# DDC118_eval2_rev1F.net
KiCad netlist of a schematic drawn in EAGLE
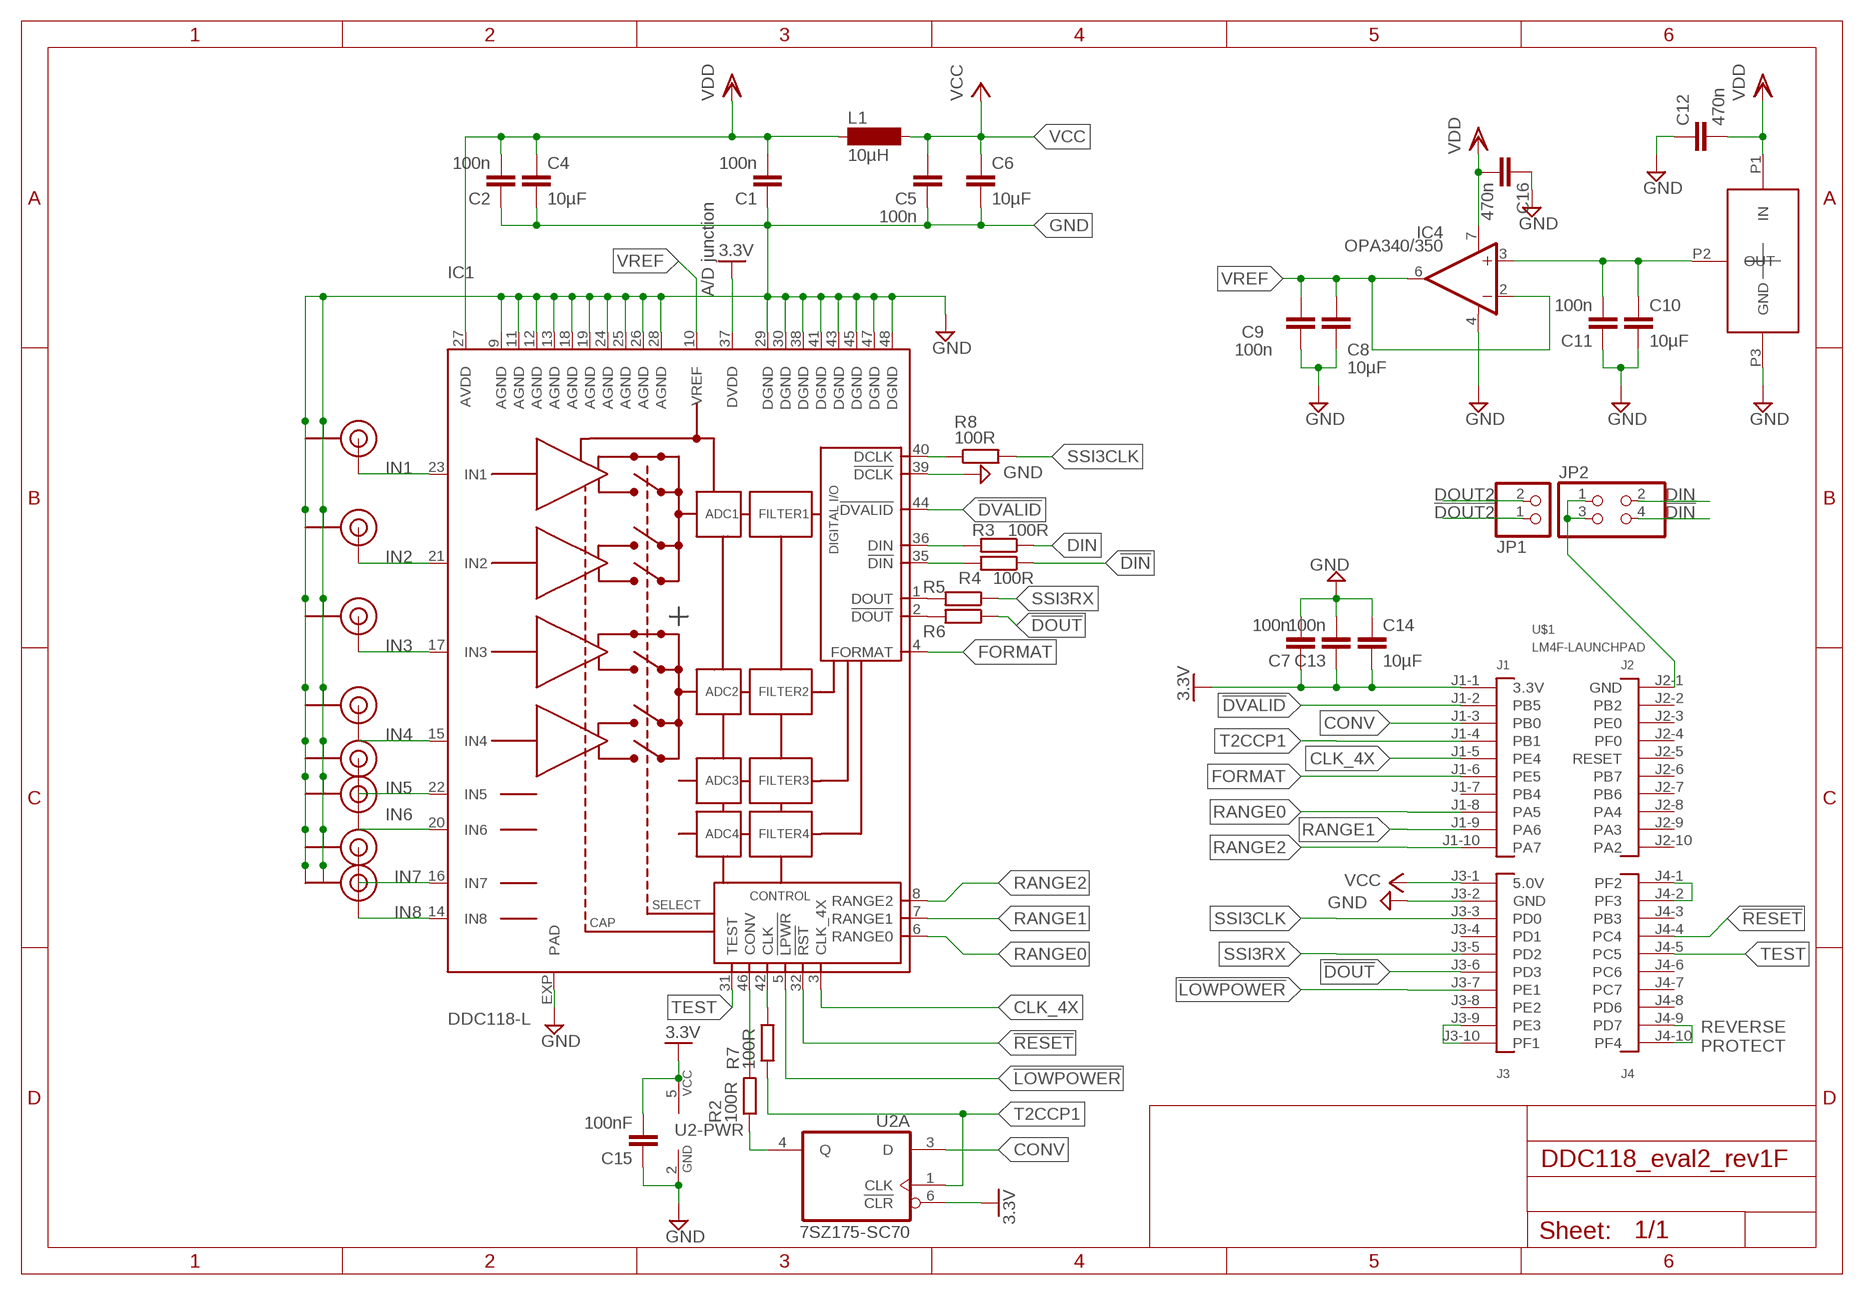
[diagram p0: schematic, sheet 1]

(export (version "E")
  (design (tool "Eeschema 10.0.6"))
  (components
    (comp (ref "C1")
      (value "100n")
      (footprint "eagle-import:C0805K")
      (libsource (lib "eagle-import") (part "C-EUC0805K"))
    )
    (comp (ref "C2")
      (value "100n")
      (footprint "eagle-import:C0805K")
      (libsource (lib "eagle-import") (part "C-EUC0805K"))
    )
    (comp (ref "C4")
      (value "10µF")
      (footprint "eagle-import:C0805")
      (libsource (lib "eagle-import") (part "C-EUC0805"))
    )
    (comp (ref "C5")
      (value "100n")
      (footprint "eagle-import:C0805K")
      (libsource (lib "eagle-import") (part "C-EUC0805K"))
    )
    (comp (ref "C6")
      (value "10µF")
      (footprint "eagle-import:C0805")
      (libsource (lib "eagle-import") (part "C-EUC0805"))
    )
    (comp (ref "C7")
      (value "100n")
      (footprint "eagle-import:C0805K")
      (libsource (lib "eagle-import") (part "C-EUC0805K"))
    )
    (comp (ref "C8")
      (value "10µF")
      (footprint "eagle-import:C0805")
      (libsource (lib "eagle-import") (part "C-EUC0805"))
    )
    (comp (ref "C9")
      (value "100n")
      (footprint "eagle-import:C0805K")
      (libsource (lib "eagle-import") (part "C-EUC0805K"))
    )
    (comp (ref "C10")
      (value "10µF")
      (footprint "eagle-import:C0805")
      (libsource (lib "eagle-import") (part "C-EUC0805"))
    )
    (comp (ref "C11")
      (value "100n")
      (footprint "eagle-import:C0805K")
      (libsource (lib "eagle-import") (part "C-EUC0805K"))
    )
    (comp (ref "C12")
      (value "470n")
      (footprint "eagle-import:C0805K")
      (libsource (lib "eagle-import") (part "C-EUC0805K"))
    )
    (comp (ref "C13")
      (value "100n")
      (footprint "eagle-import:C0805K")
      (libsource (lib "eagle-import") (part "C-EUC0805K"))
    )
    (comp (ref "C14")
      (value "10µF")
      (footprint "eagle-import:C0805")
      (libsource (lib "eagle-import") (part "C-EUC0805"))
    )
    (comp (ref "C15")
      (value "100nF")
      (footprint "eagle-import:C0603K")
      (libsource (lib "eagle-import") (part "resistor_C-EUC0603K"))
    )
    (comp (ref "C16")
      (value "470n")
      (footprint "eagle-import:0805")
      (libsource (lib "eagle-import") (part "CAP0805"))
    )
    (comp (ref "IC1")
      (value "DDC118-L")
      (footprint "eagle-import:VQFN48-L")
      (libsource (lib "eagle-import") (part "DDC118-L"))
    )
    (comp (ref "IC4")
      (value "OPA340/350")
      (footprint "eagle-import:SO08")
      (fields (field (name "MPN") "OPA340UA"))
      (libsource (lib "eagle-import") (part "OPA340U"))
    )
    (comp (ref "JP1")
      (value "PINHD-1X2_2.54-SMD")
      (footprint "eagle-import:1X02SMD")
      (libsource (lib "eagle-import") (part "PINHD-1X2_2.54-SMD"))
    )
    (comp (ref "JP2")
      (value "PINHD-2X2_2.54-SMD")
      (footprint "eagle-import:2X02SMD")
      (libsource (lib "eagle-import") (part "PINHD-2X2_2.54-SMD"))
    )
    (comp (ref "L1")
      (value "10µH")
      (footprint "eagle-import:MS50")
      (libsource (lib "eagle-import") (part "MS50"))
    )
    (comp (ref "R2")
      (value "100R")
      (footprint "eagle-import:R0402")
      (libsource (lib "eagle-import") (part "R-EU_R0402"))
    )
    (comp (ref "R3")
      (value "100R")
      (footprint "eagle-import:R0402")
      (libsource (lib "eagle-import") (part "R-EU_R0402"))
    )
    (comp (ref "R4")
      (value "100R")
      (footprint "eagle-import:R0402")
      (libsource (lib "eagle-import") (part "R-EU_R0402"))
    )
    (comp (ref "R5")
      (value "100R")
      (footprint "eagle-import:R0402")
      (libsource (lib "eagle-import") (part "R-EU_R0402"))
    )
    (comp (ref "R6")
      (value "100R")
      (footprint "eagle-import:R0402")
      (libsource (lib "eagle-import") (part "R-EU_R0402"))
    )
    (comp (ref "R7")
      (value "100R")
      (footprint "eagle-import:R0402")
      (libsource (lib "eagle-import") (part "R-EU_R0402"))
    )
    (comp (ref "R8")
      (value "100R")
      (footprint "eagle-import:R0402")
      (libsource (lib "eagle-import") (part "R-EU_R0402"))
    )
    (comp (ref "U$1")
      (value "LM4F-LAUNCHPAD")
      (footprint "eagle-import:LM4F120-LAUNCHPAD")
      (libsource (lib "eagle-import") (part "LM4F-LAUNCHPAD"))
    )
    (comp (ref "U$4")
      (value "U.FL")
      (footprint "eagle-import:U.FL")
      (libsource (lib "eagle-import") (part "U.FL"))
    )
    (comp (ref "U$5")
      (value "U.FL")
      (footprint "eagle-import:U.FL")
      (libsource (lib "eagle-import") (part "U.FL"))
    )
    (comp (ref "U$6")
      (value "U.FL")
      (footprint "eagle-import:U.FL")
      (libsource (lib "eagle-import") (part "U.FL"))
    )
    (comp (ref "U$7")
      (value "U.FL")
      (footprint "eagle-import:U.FL")
      (libsource (lib "eagle-import") (part "U.FL"))
    )
    (comp (ref "U$8")
      (value "U.FL")
      (footprint "eagle-import:U.FL")
      (libsource (lib "eagle-import") (part "U.FL"))
    )
    (comp (ref "U$9")
      (value "U.FL")
      (footprint "eagle-import:U.FL")
      (libsource (lib "eagle-import") (part "U.FL"))
    )
    (comp (ref "U$10")
      (value "U.FL")
      (footprint "eagle-import:U.FL")
      (libsource (lib "eagle-import") (part "U.FL"))
    )
    (comp (ref "U$11")
      (value "U.FL")
      (footprint "eagle-import:U.FL")
      (libsource (lib "eagle-import") (part "U.FL"))
    )
    (comp (ref "U1")
      (value "REF30XX")
      (footprint "eagle-import:SOT-23")
      (libsource (lib "eagle-import") (part "REF30XX"))
    )
    (comp (ref "U2")
      (value "7SZ175-SC70")
      (footprint "eagle-import:SC-70")
      (libsource (lib "eagle-import") (part "7SZ175-SC70"))
    )
  )
  (nets
    (net (code "1") (name "/DOUT2") (class "Default")
      (node (ref "JP1") (pin "2") (pinfunction "2_2") (pintype "passive"))
    )
    (net (code "2") (name "/IN1") (class "Default")
      (node (ref "IC1") (pin "23") (pinfunction "IN1_23") (pintype "input"))
      (node (ref "U$5") (pin "P$3") (pinfunction "SIGNAL_P$3") (pintype "bidirectional"))
    )
    (net (code "3") (name "/IN2") (class "Default")
      (node (ref "IC1") (pin "21") (pinfunction "IN2_21") (pintype "input"))
      (node (ref "U$6") (pin "P$3") (pinfunction "SIGNAL_P$3") (pintype "bidirectional"))
    )
    (net (code "4") (name "/IN3") (class "Default")
      (node (ref "IC1") (pin "17") (pinfunction "IN3_17") (pintype "input"))
      (node (ref "U$7") (pin "P$3") (pinfunction "SIGNAL_P$3") (pintype "bidirectional"))
    )
    (net (code "5") (name "/IN4") (class "Default")
      (node (ref "IC1") (pin "15") (pinfunction "IN4_15") (pintype "input"))
      (node (ref "U$8") (pin "P$3") (pinfunction "SIGNAL_P$3") (pintype "bidirectional"))
    )
    (net (code "6") (name "/IN5") (class "Default")
      (node (ref "IC1") (pin "22") (pinfunction "IN5_22") (pintype "input"))
      (node (ref "U$9") (pin "P$3") (pinfunction "SIGNAL_P$3") (pintype "bidirectional"))
    )
    (net (code "7") (name "/IN6") (class "Default")
      (node (ref "IC1") (pin "20") (pinfunction "IN6_20") (pintype "input"))
      (node (ref "U$4") (pin "P$3") (pinfunction "SIGNAL_P$3") (pintype "bidirectional"))
    )
    (net (code "8") (name "/IN7") (class "Default")
      (node (ref "IC1") (pin "16") (pinfunction "IN7_16") (pintype "input"))
      (node (ref "U$11") (pin "P$3") (pinfunction "SIGNAL_P$3") (pintype "bidirectional"))
    )
    (net (code "9") (name "/IN8") (class "Default")
      (node (ref "IC1") (pin "14") (pinfunction "IN8_14") (pintype "input"))
      (node (ref "U$10") (pin "P$3") (pinfunction "SIGNAL_P$3") (pintype "bidirectional"))
    )
    (net (code "10") (name "/~{DIN}") (class "Default")
      (node (ref "JP2") (pin "4") (pinfunction "4_4") (pintype "passive"))
      (node (ref "R4") (pin "1") (pinfunction "1_1") (pintype "passive"))
    )
    (net (code "11") (name "/~{DOUT2}") (class "Default")
      (node (ref "JP1") (pin "1") (pinfunction "1_1") (pintype "passive"))
    )
    (net (code "12") (name "/~{DOUT}") (class "Default")
      (node (ref "R6") (pin "1") (pinfunction "1_1") (pintype "passive"))
      (node (ref "U$1") (pin "J3-6") (pinfunction "PD3_J3-6") (pintype "bidirectional"))
    )
    (net (code "13") (name "/~{DVALID}") (class "Default")
      (node (ref "IC1") (pin "44") (pinfunction "~{DVALID}_44") (pintype "output"))
      (node (ref "U$1") (pin "J1-2") (pinfunction "PB5_J1-2") (pintype "bidirectional"))
    )
    (net (code "14") (name "/~{LOWPOWER}") (class "Default")
      (node (ref "IC1") (pin "5") (pinfunction "~{LPWR}_5") (pintype "input"))
      (node (ref "U$1") (pin "J3-7") (pinfunction "PE1_J3-7") (pintype "bidirectional"))
    )
    (net (code "15") (name "/~{RESET}") (class "Default")
      (node (ref "IC1") (pin "32") (pinfunction "~{RST}_32") (pintype "input"))
      (node (ref "U$1") (pin "J4-4") (pinfunction "PC4_J4-4") (pintype "bidirectional"))
    )
    (net (code "16") (name "3.3V") (class "Default")
      (node (ref "C13") (pin "1") (pinfunction "1_1") (pintype "passive"))
      (node (ref "C14") (pin "2") (pinfunction "2_2") (pintype "passive"))
      (node (ref "C15") (pin "2") (pinfunction "2_2") (pintype "passive"))
      (node (ref "C7") (pin "1") (pinfunction "1_1") (pintype "passive"))
      (node (ref "IC1") (pin "37") (pinfunction "DVDD_37") (pintype "power_in"))
      (node (ref "U$1") (pin "J1-1") (pinfunction "3.3V_J1-1") (pintype "power_in"))
      (node (ref "U2") (pin "5") (pinfunction "VCC_5") (pintype "power_in"))
      (node (ref "U2") (pin "6") (pinfunction "~{CLR}_6") (pintype "input"))
    )
    (net (code "17") (name "CLK_4X") (class "Default")
      (node (ref "IC1") (pin "3") (pinfunction "CLK_4X_3") (pintype "input"))
      (node (ref "U$1") (pin "J1-5") (pinfunction "PE4_J1-5") (pintype "bidirectional"))
    )
    (net (code "18") (name "CONV") (class "Default")
      (node (ref "U$1") (pin "J1-3") (pinfunction "PB0_J1-3") (pintype "bidirectional"))
      (node (ref "U2") (pin "3") (pinfunction "D_3") (pintype "input"))
    )
    (net (code "19") (name "DIN") (class "Default")
      (node (ref "JP2") (pin "2") (pinfunction "2_2") (pintype "passive"))
      (node (ref "R3") (pin "1") (pinfunction "1_1") (pintype "passive"))
    )
    (net (code "20") (name "FORMAT") (class "Default")
      (node (ref "IC1") (pin "4") (pinfunction "FORMAT_4") (pintype "output"))
      (node (ref "U$1") (pin "J1-6") (pinfunction "PE5_J1-6") (pintype "bidirectional"))
    )
    (net (code "21") (name "GND") (class "Default")
      (node (ref "C1") (pin "1") (pinfunction "1_1") (pintype "passive"))
      (node (ref "C10") (pin "2") (pinfunction "2_2") (pintype "passive"))
      (node (ref "C11") (pin "1") (pinfunction "1_1") (pintype "passive"))
      (node (ref "C12") (pin "1") (pinfunction "1_1") (pintype "passive"))
      (node (ref "C13") (pin "2") (pinfunction "2_2") (pintype "passive"))
      (node (ref "C14") (pin "1") (pinfunction "1_1") (pintype "passive"))
      (node (ref "C15") (pin "1") (pinfunction "1_1") (pintype "passive"))
      (node (ref "C16") (pin "1") (pinfunction "1_1") (pintype "passive"))
      (node (ref "C2") (pin "1") (pinfunction "1_1") (pintype "passive"))
      (node (ref "C4") (pin "2") (pinfunction "2_2") (pintype "passive"))
      (node (ref "C5") (pin "1") (pinfunction "1_1") (pintype "passive"))
      (node (ref "C6") (pin "2") (pinfunction "2_2") (pintype "passive"))
      (node (ref "C7") (pin "2") (pinfunction "2_2") (pintype "passive"))
      (node (ref "C8") (pin "2") (pinfunction "2_2") (pintype "passive"))
      (node (ref "C9") (pin "1") (pinfunction "1_1") (pintype "passive"))
      (node (ref "IC1") (pin "11") (pinfunction "AGND_11") (pintype "power_in"))
      (node (ref "IC1") (pin "12") (pinfunction "AGND_12") (pintype "power_in"))
      (node (ref "IC1") (pin "13") (pinfunction "AGND_13") (pintype "power_in"))
      (node (ref "IC1") (pin "18") (pinfunction "AGND_18") (pintype "power_in"))
      (node (ref "IC1") (pin "19") (pinfunction "AGND_19") (pintype "power_in"))
      (node (ref "IC1") (pin "24") (pinfunction "AGND_24") (pintype "power_in"))
      (node (ref "IC1") (pin "25") (pinfunction "AGND_25") (pintype "power_in"))
      (node (ref "IC1") (pin "26") (pinfunction "AGND_26") (pintype "power_in"))
      (node (ref "IC1") (pin "28") (pinfunction "AGND_28") (pintype "power_in"))
      (node (ref "IC1") (pin "29") (pinfunction "DGND_29") (pintype "power_in"))
      (node (ref "IC1") (pin "30") (pinfunction "DGND_30") (pintype "power_in"))
      (node (ref "IC1") (pin "38") (pinfunction "DGND_38") (pintype "power_in"))
      (node (ref "IC1") (pin "39") (pinfunction "~{DCLK}_39") (pintype "input"))
      (node (ref "IC1") (pin "41") (pinfunction "DGND_41") (pintype "power_in"))
      (node (ref "IC1") (pin "43") (pinfunction "DGND_43") (pintype "power_in"))
      (node (ref "IC1") (pin "45") (pinfunction "DGND_45") (pintype "power_in"))
      (node (ref "IC1") (pin "47") (pinfunction "DGND_47") (pintype "power_in"))
      (node (ref "IC1") (pin "48") (pinfunction "DGND_48") (pintype "power_in"))
      (node (ref "IC1") (pin "9") (pinfunction "AGND_9") (pintype "power_in"))
      (node (ref "IC1") (pin "EXP") (pinfunction "PAD_EXP") (pintype "power_in"))
      (node (ref "IC4") (pin "4") (pinfunction "V-_4") (pintype "power_in"))
      (node (ref "U$1") (pin "J3-2") (pinfunction "GND_J3-2") (pintype "bidirectional"))
      (node (ref "U$10") (pin "P$1") (pinfunction "GND_P$1") (pintype "bidirectional"))
      (node (ref "U$10") (pin "P$2") (pinfunction "GND_P$2") (pintype "bidirectional"))
      (node (ref "U$11") (pin "P$1") (pinfunction "GND_P$1") (pintype "bidirectional"))
      (node (ref "U$11") (pin "P$2") (pinfunction "GND_P$2") (pintype "bidirectional"))
      (node (ref "U$4") (pin "P$1") (pinfunction "GND_P$1") (pintype "bidirectional"))
      (node (ref "U$4") (pin "P$2") (pinfunction "GND_P$2") (pintype "bidirectional"))
      (node (ref "U$5") (pin "P$1") (pinfunction "GND_P$1") (pintype "bidirectional"))
      (node (ref "U$5") (pin "P$2") (pinfunction "GND_P$2") (pintype "bidirectional"))
      (node (ref "U$6") (pin "P$1") (pinfunction "GND_P$1") (pintype "bidirectional"))
      (node (ref "U$6") (pin "P$2") (pinfunction "GND_P$2") (pintype "bidirectional"))
      (node (ref "U$7") (pin "P$1") (pinfunction "GND_P$1") (pintype "bidirectional"))
      (node (ref "U$7") (pin "P$2") (pinfunction "GND_P$2") (pintype "bidirectional"))
      (node (ref "U$8") (pin "P$1") (pinfunction "GND_P$1") (pintype "bidirectional"))
      (node (ref "U$8") (pin "P$2") (pinfunction "GND_P$2") (pintype "bidirectional"))
      (node (ref "U$9") (pin "P$1") (pinfunction "GND_P$1") (pintype "bidirectional"))
      (node (ref "U$9") (pin "P$2") (pinfunction "GND_P$2") (pintype "bidirectional"))
      (node (ref "U1") (pin "P3") (pinfunction "GND_P3") (pintype "bidirectional"))
      (node (ref "U2") (pin "2") (pinfunction "GND_2") (pintype "power_in"))
    )
    (net (code "22") (name "Net-(IC1-CLK)") (class "Default")
      (node (ref "IC1") (pin "42") (pinfunction "CLK_42") (pintype "input"))
      (node (ref "R7") (pin "2") (pinfunction "2_2") (pintype "passive"))
    )
    (net (code "23") (name "Net-(IC1-CONV)") (class "Default")
      (node (ref "IC1") (pin "46") (pinfunction "CONV_46") (pintype "input"))
      (node (ref "R2") (pin "2") (pinfunction "2_2") (pintype "passive"))
    )
    (net (code "24") (name "Net-(IC1-DCLK)") (class "Default")
      (node (ref "IC1") (pin "40") (pinfunction "DCLK_40") (pintype "input"))
      (node (ref "R8") (pin "1") (pinfunction "1_1") (pintype "passive"))
    )
    (net (code "25") (name "Net-(IC1-DIN)") (class "Default")
      (node (ref "IC1") (pin "36") (pinfunction "DIN_36") (pintype "input"))
      (node (ref "R3") (pin "2") (pinfunction "2_2") (pintype "passive"))
    )
    (net (code "26") (name "Net-(IC1-DOUT)") (class "Default")
      (node (ref "IC1") (pin "1") (pinfunction "DOUT_1") (pintype "output"))
      (node (ref "R5") (pin "2") (pinfunction "2_2") (pintype "passive"))
    )
    (net (code "27") (name "Net-(IC1-~{DIN})") (class "Default")
      (node (ref "IC1") (pin "35") (pinfunction "~{DIN}_35") (pintype "input"))
      (node (ref "R4") (pin "2") (pinfunction "2_2") (pintype "passive"))
    )
    (net (code "28") (name "Net-(IC1-~{DOUT})") (class "Default")
      (node (ref "IC1") (pin "2") (pinfunction "~{DOUT}_2") (pintype "output"))
      (node (ref "R6") (pin "2") (pinfunction "2_2") (pintype "passive"))
    )
    (net (code "29") (name "Net-(IC4-+IN)") (class "Default")
      (node (ref "C10") (pin "1") (pinfunction "1_1") (pintype "passive"))
      (node (ref "C11") (pin "2") (pinfunction "2_2") (pintype "passive"))
      (node (ref "IC4") (pin "3") (pinfunction "+IN_3") (pintype "input"))
      (node (ref "U1") (pin "P2") (pinfunction "OUT_P2") (pintype "bidirectional"))
    )
    (net (code "30") (name "Net-(JP2-Pad1)") (class "Default")
      (node (ref "JP2") (pin "1") (pinfunction "1_1") (pintype "passive"))
      (node (ref "JP2") (pin "3") (pinfunction "3_3") (pintype "passive"))
      (node (ref "U$1") (pin "J2-1") (pinfunction "GND_J2-1") (pintype "power_in"))
    )
    (net (code "31") (name "Net-(U$1-PD7)") (class "Default")
      (node (ref "U$1") (pin "J4-10") (pinfunction "PF4_J4-10") (pintype "bidirectional"))
      (node (ref "U$1") (pin "J4-9") (pinfunction "PD7_J4-9") (pintype "bidirectional"))
    )
    (net (code "32") (name "Net-(U$1-PE3)") (class "Default")
      (node (ref "U$1") (pin "J3-10") (pinfunction "PF1_J3-10") (pintype "bidirectional"))
      (node (ref "U$1") (pin "J3-9") (pinfunction "PE3_J3-9") (pintype "bidirectional"))
    )
    (net (code "33") (name "Net-(U$1-PF2)") (class "Default")
      (node (ref "U$1") (pin "J4-1") (pinfunction "PF2_J4-1") (pintype "power_in"))
      (node (ref "U$1") (pin "J4-2") (pinfunction "PF3_J4-2") (pintype "bidirectional"))
    )
    (net (code "34") (name "Net-(U2B-Q)") (class "Default")
      (node (ref "R2") (pin "1") (pinfunction "1_1") (pintype "passive"))
      (node (ref "U2") (pin "4") (pinfunction "Q_4") (pintype "output"))
    )
    (net (code "35") (name "RANGE0") (class "Default")
      (node (ref "IC1") (pin "6") (pinfunction "RANGE0_6") (pintype "output"))
      (node (ref "U$1") (pin "J1-8") (pinfunction "PA5_J1-8") (pintype "bidirectional"))
    )
    (net (code "36") (name "RANGE1") (class "Default")
      (node (ref "IC1") (pin "7") (pinfunction "RANGE1_7") (pintype "output"))
      (node (ref "U$1") (pin "J1-9") (pinfunction "PA6_J1-9") (pintype "bidirectional"))
    )
    (net (code "37") (name "RANGE2") (class "Default")
      (node (ref "IC1") (pin "8") (pinfunction "RANGE2_8") (pintype "output"))
      (node (ref "U$1") (pin "J1-10") (pinfunction "PA7_J1-10") (pintype "bidirectional"))
    )
    (net (code "38") (name "SSI3CLK") (class "Default")
      (node (ref "R8") (pin "2") (pinfunction "2_2") (pintype "passive"))
      (node (ref "U$1") (pin "J3-3") (pinfunction "PD0_J3-3") (pintype "bidirectional"))
    )
    (net (code "39") (name "SSI3RX") (class "Default")
      (node (ref "R5") (pin "1") (pinfunction "1_1") (pintype "passive"))
      (node (ref "U$1") (pin "J3-5") (pinfunction "PD2_J3-5") (pintype "bidirectional"))
    )
    (net (code "40") (name "T2CCP1") (class "Default")
      (node (ref "R7") (pin "1") (pinfunction "1_1") (pintype "passive"))
      (node (ref "U$1") (pin "J1-4") (pinfunction "PB1_J1-4") (pintype "bidirectional"))
      (node (ref "U2") (pin "1") (pinfunction "CLK_1") (pintype "input"))
    )
    (net (code "41") (name "TEST") (class "Default")
      (node (ref "IC1") (pin "31") (pinfunction "TEST_31") (pintype "power_in"))
      (node (ref "U$1") (pin "J4-5") (pinfunction "PC5_J4-5") (pintype "bidirectional"))
    )
    (net (code "42") (name "VCC") (class "Default")
      (node (ref "C5") (pin "2") (pinfunction "2_2") (pintype "passive"))
      (node (ref "C6") (pin "1") (pinfunction "1_1") (pintype "passive"))
      (node (ref "L1") (pin "2") (pinfunction "2_2") (pintype "passive"))
      (node (ref "U$1") (pin "J3-1") (pinfunction "5.0V_J3-1") (pintype "power_in"))
    )
    (net (code "43") (name "VDD") (class "Default")
      (node (ref "C1") (pin "2") (pinfunction "2_2") (pintype "passive"))
      (node (ref "C12") (pin "2") (pinfunction "2_2") (pintype "passive"))
      (node (ref "C16") (pin "2") (pinfunction "2_2") (pintype "passive"))
      (node (ref "C2") (pin "2") (pinfunction "2_2") (pintype "passive"))
      (node (ref "C4") (pin "1") (pinfunction "1_1") (pintype "passive"))
      (node (ref "IC1") (pin "27") (pinfunction "AVDD_27") (pintype "power_in"))
      (node (ref "IC4") (pin "7") (pinfunction "V+_7") (pintype "power_in"))
      (node (ref "L1") (pin "1") (pinfunction "1_1") (pintype "passive"))
      (node (ref "U1") (pin "P1") (pinfunction "IN_P1") (pintype "bidirectional"))
    )
    (net (code "44") (name "VREF") (class "Default")
      (node (ref "C8") (pin "1") (pinfunction "1_1") (pintype "passive"))
      (node (ref "C9") (pin "2") (pinfunction "2_2") (pintype "passive"))
      (node (ref "IC1") (pin "10") (pinfunction "VREF_10") (pintype "passive"))
      (node (ref "IC4") (pin "2") (pinfunction "-IN_2") (pintype "input"))
      (node (ref "IC4") (pin "6") (pinfunction "OUT_6") (pintype "output"))
    )
    (net (code "45") (name "unconnected-(U$1-PA2-PadJ2-10)") (class "Default")
      (node (ref "U$1") (pin "J2-10") (pinfunction "PA2_J2-10") (pintype "bidirectional"))
    )
    (net (code "46") (name "unconnected-(U$1-PA3-PadJ2-9)") (class "Default")
      (node (ref "U$1") (pin "J2-9") (pinfunction "PA3_J2-9") (pintype "bidirectional"))
    )
    (net (code "47") (name "unconnected-(U$1-PA4-PadJ2-8)") (class "Default")
      (node (ref "U$1") (pin "J2-8") (pinfunction "PA4_J2-8") (pintype "bidirectional"))
    )
    (net (code "48") (name "unconnected-(U$1-PB2-PadJ2-2)") (class "Default")
      (node (ref "U$1") (pin "J2-2") (pinfunction "PB2_J2-2") (pintype "bidirectional"))
    )
    (net (code "49") (name "unconnected-(U$1-PB3-PadJ4-3)") (class "Default")
      (node (ref "U$1") (pin "J4-3") (pinfunction "PB3_J4-3") (pintype "bidirectional"))
    )
    (net (code "50") (name "unconnected-(U$1-PB4-PadJ1-7)") (class "Default")
      (node (ref "U$1") (pin "J1-7") (pinfunction "PB4_J1-7") (pintype "bidirectional"))
    )
    (net (code "51") (name "unconnected-(U$1-PB6-PadJ2-7)") (class "Default")
      (node (ref "U$1") (pin "J2-7") (pinfunction "PB6_J2-7") (pintype "bidirectional"))
    )
    (net (code "52") (name "unconnected-(U$1-PB7-PadJ2-6)") (class "Default")
      (node (ref "U$1") (pin "J2-6") (pinfunction "PB7_J2-6") (pintype "bidirectional"))
    )
    (net (code "53") (name "unconnected-(U$1-PC6-PadJ4-6)") (class "Default")
      (node (ref "U$1") (pin "J4-6") (pinfunction "PC6_J4-6") (pintype "bidirectional"))
    )
    (net (code "54") (name "unconnected-(U$1-PC7-PadJ4-7)") (class "Default")
      (node (ref "U$1") (pin "J4-7") (pinfunction "PC7_J4-7") (pintype "bidirectional"))
    )
    (net (code "55") (name "unconnected-(U$1-PD1-PadJ3-4)") (class "Default")
      (node (ref "U$1") (pin "J3-4") (pinfunction "PD1_J3-4") (pintype "bidirectional"))
    )
    (net (code "56") (name "unconnected-(U$1-PD6-PadJ4-8)") (class "Default")
      (node (ref "U$1") (pin "J4-8") (pinfunction "PD6_J4-8") (pintype "bidirectional"))
    )
    (net (code "57") (name "unconnected-(U$1-PE0-PadJ2-3)") (class "Default")
      (node (ref "U$1") (pin "J2-3") (pinfunction "PE0_J2-3") (pintype "bidirectional"))
    )
    (net (code "58") (name "unconnected-(U$1-PE2-PadJ3-8)") (class "Default")
      (node (ref "U$1") (pin "J3-8") (pinfunction "PE2_J3-8") (pintype "bidirectional"))
    )
    (net (code "59") (name "unconnected-(U$1-PF0-PadJ2-4)") (class "Default")
      (node (ref "U$1") (pin "J2-4") (pinfunction "PF0_J2-4") (pintype "bidirectional"))
    )
    (net (code "60") (name "unconnected-(U$1-RESET-PadJ2-5)") (class "Default")
      (node (ref "U$1") (pin "J2-5") (pinfunction "RESET_J2-5") (pintype "bidirectional"))
    )
  )
)
